# PWM-24Route.net
KiCad netlist of a schematic drawn in EasyEDA Pro
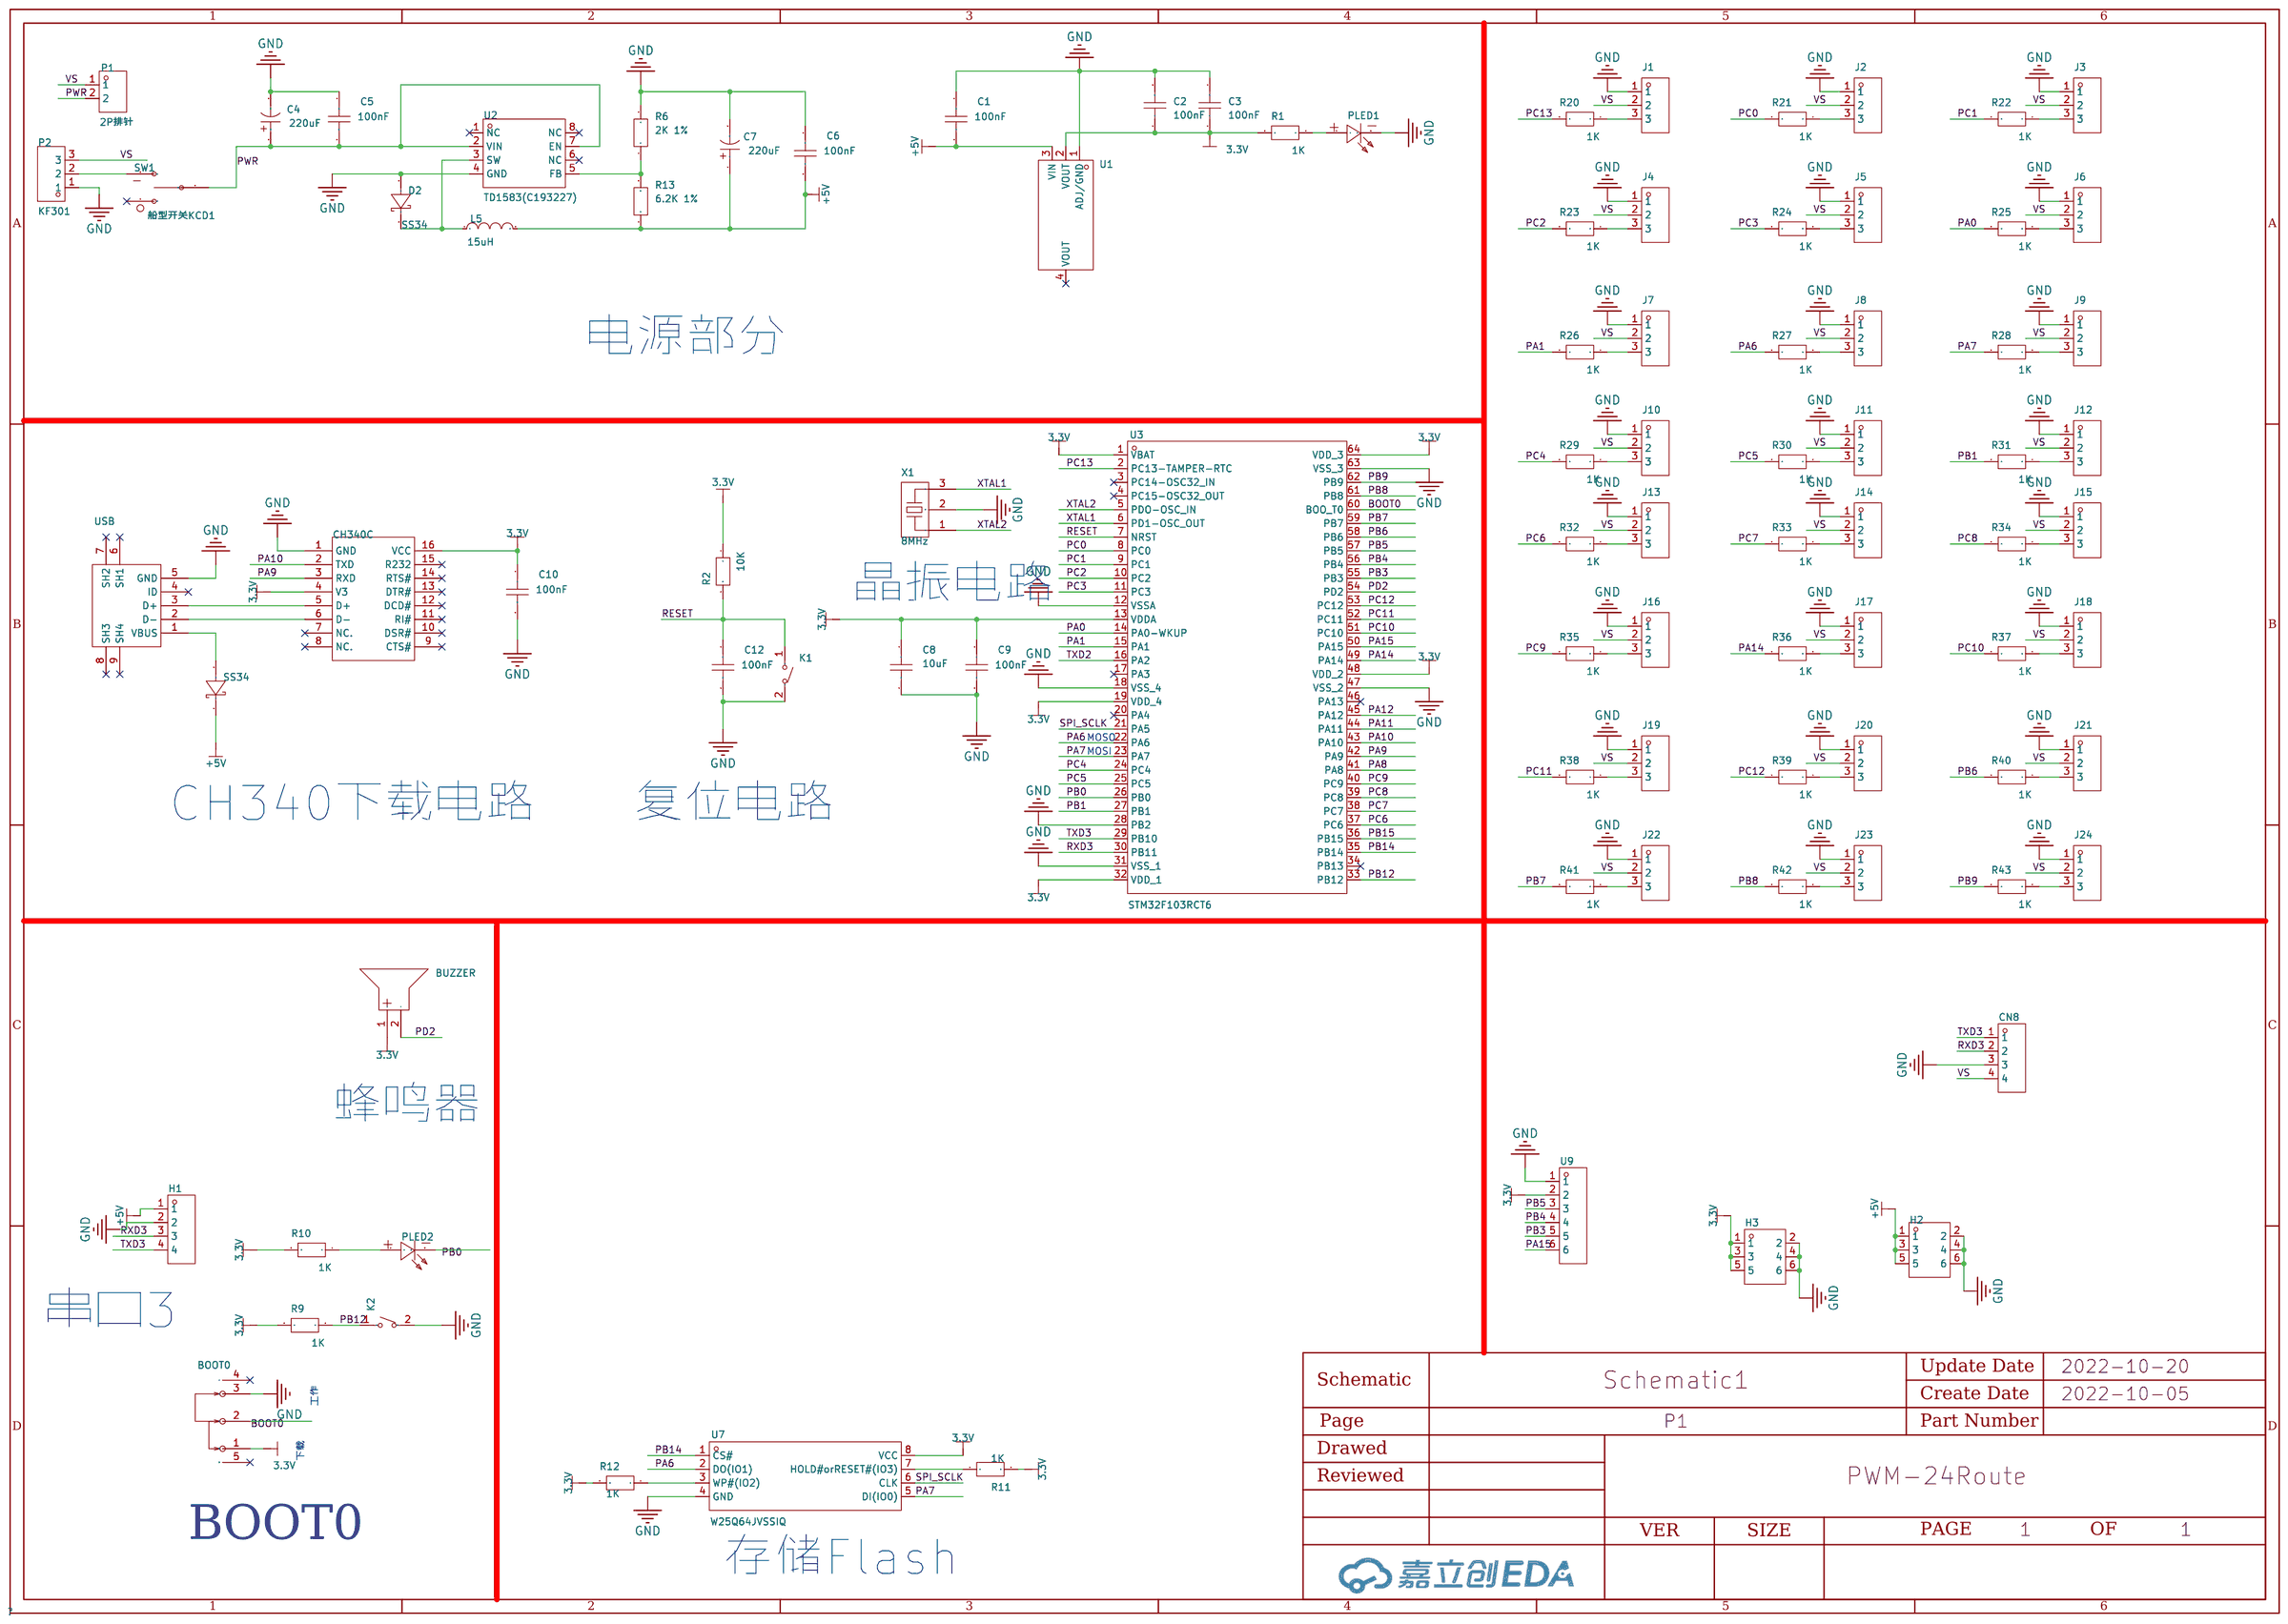
[diagram p0: schematic sheet]

(export (version "E")
  (design (tool "Eeschema 10.0.6"))
  (components
    (comp (ref "BOOT0")
      (value "SS-12F44-G5")
      (footprint "easyedapro:SW-TH_SS-12F44-G5")
      (fields (field (name "Manufacturer") "USAKRO(美韩)"))
      (libsource (lib "easyedapro") (part "SS-12F44-G5_C620367"))
    )
    (comp (ref "BUZZER")
      (value "5V,管脚间距8mm,外径10mm,高9.5mm")
      (footprint "easyedapro:BUZ-TH_BD12.0-P7.60-D0.6-FD")
      (libsource (lib "easyedapro") (part "5V,管脚间距8MM,外径10MM,高9.5MM"))
    )
    (comp (ref "C1")
      (value "100nF")
      (footprint "easyedapro:C0603")
      (description "容值:100nF;精度:±10%;额定电压:25V;温度系数:X7R;")
      (fields (field (name "Manufacturer Part") "C0603C104K3RAC") (field (name "Manufacturer") "KEMET(基美)"))
      (libsource (lib "easyedapro") (part "C0603C104K3RAC"))
    )
    (comp (ref "C2")
      (value "100nF")
      (footprint "easyedapro:C0603")
      (description "容值:100nF;精度:±10%;额定电压:25V;温度系数:X7R;")
      (fields (field (name "Manufacturer Part") "C0603C104K3RAC") (field (name "Manufacturer") "KEMET(基美)"))
      (libsource (lib "easyedapro") (part "C0603C104K3RAC"))
    )
    (comp (ref "C3")
      (value "100nF")
      (footprint "easyedapro:C0603")
      (description "容值:100nF;精度:±10%;额定电压:25V;温度系数:X7R;")
      (fields (field (name "Manufacturer Part") "C0603C104K3RAC") (field (name "Manufacturer") "KEMET(基美)"))
      (libsource (lib "easyedapro") (part "C0603C104K3RAC"))
    )
    (comp (ref "C4")
      (value "220uF")
      (footprint "easyedapro:CAP-SMD_BD6.3-L6.6-W6.6-FD")
      (description "容值:220uF;额定电压:16V;工作寿命:2000hrs@105;")
      (fields
        (field (name "Manufacturer Part") "RVT220UF16V67RV0015")
        (field (name "Manufacturer") "KNSCHA(科尼盛)")
      )
      (libsource (lib "easyedapro") (part "RVT220UF16V67RV0015"))
    )
    (comp (ref "C5")
      (value "100nF")
      (footprint "easyedapro:C0603")
      (description "容值:100nF;精度:±10%;额定电压:25V;温度系数:X7R;")
      (fields (field (name "Manufacturer Part") "C0603C104K3RAC") (field (name "Manufacturer") "KEMET(基美)"))
      (libsource (lib "easyedapro") (part "C0603C104K3RAC"))
    )
    (comp (ref "C6")
      (value "100nF")
      (footprint "easyedapro:C0603")
      (description "容值:100nF;精度:±10%;额定电压:25V;温度系数:X7R;")
      (fields (field (name "Manufacturer Part") "C0603C104K3RAC") (field (name "Manufacturer") "KEMET(基美)"))
      (libsource (lib "easyedapro") (part "C0603C104K3RAC"))
    )
    (comp (ref "C7")
      (value "220uF")
      (footprint "easyedapro:CAP-SMD_BD6.3-L6.6-W6.6-FD")
      (description "容值:220uF;额定电压:16V;工作寿命:2000hrs@105;")
      (fields
        (field (name "Manufacturer Part") "RVT220UF16V67RV0015")
        (field (name "Manufacturer") "KNSCHA(科尼盛)")
      )
      (libsource (lib "easyedapro") (part "RVT220UF16V67RV0015"))
    )
    (comp (ref "C8")
      (value "10uF")
      (footprint "easyedapro:C0603")
      (description "容值:100nF;精度:±10%;额定电压:25V;温度系数:X7R;")
      (fields (field (name "Manufacturer Part") "C0603C104K3RAC") (field (name "Manufacturer") "KEMET(基美)"))
      (libsource (lib "easyedapro") (part "C0603C104K3RAC"))
    )
    (comp (ref "C9")
      (value "100nF")
      (footprint "easyedapro:C0603")
      (description "容值:100nF;精度:±10%;额定电压:25V;温度系数:X7R;")
      (fields (field (name "Manufacturer Part") "C0603C104K3RAC") (field (name "Manufacturer") "KEMET(基美)"))
      (libsource (lib "easyedapro") (part "C0603C104K3RAC"))
    )
    (comp (ref "C10")
      (value "100nF")
      (footprint "easyedapro:C0603")
      (description "容值:100nF;精度:±10%;额定电压:25V;温度系数:X7R;")
      (fields (field (name "Manufacturer Part") "C0603C104K3RAC") (field (name "Manufacturer") "KEMET(基美)"))
      (libsource (lib "easyedapro") (part "C0603C104K3RAC"))
    )
    (comp (ref "C12")
      (value "100nF")
      (footprint "easyedapro:C0603")
      (description "容值:100nF;精度:±10%;额定电压:25V;温度系数:X7R;")
      (fields (field (name "Manufacturer Part") "C0603C104K3RAC") (field (name "Manufacturer") "KEMET(基美)"))
      (libsource (lib "easyedapro") (part "C0603C104K3RAC"))
    )
    (comp (ref "CH340C")
      (value "CH340C")
      (footprint "easyedapro:SOP-16_L10.0-W3.9-P1.27-LS6.0-BL")
      (description "类型:Transceiver;协议类别:USB 2.0;驱动器/接收器数:-;数据速率:2Mbps;")
      (fields (field (name "Manufacturer") "WCH(南京沁恒)"))
      (libsource (lib "easyedapro") (part "CH340C"))
    )
    (comp (ref "CN8")
      (value "HC-5264-4AW")
      (footprint "easyedapro:CONN-TH_4P-P2.50_HCTL_HC-5264-4AW")
      (description "参考系列:-;间距:2.5mm;插针结构:1x4P;排数:1;每排PIN数:4;行距:-;公母:公型插针;安装方式:弯插;额定电流:3A;工作温度范围:-25~+85;")
      (fields (field (name "Manufacturer") "HCTL(华灿天禄)"))
      (libsource (lib "easyedapro") (part "HC-5264-4AW"))
    )
    (comp (ref "D2")
      (value "SS34")
      (footprint "easyedapro:SMA_L4.3-W2.6-LS5.2-RD")
      (fields (field (name "Manufacturer") "TDD(台冠电子)"))
      (libsource (lib "easyedapro") (part "SS34_C3032484"))
    )
    (comp (ref "H1")
      (value "PM2.54-1*4")
      (footprint "easyedapro:HDR-TH_4P-P2.54-V-F")
      (description "安装类型:直插;")
      (fields (field (name "Manufacturer") "ZHOURI(洲日)"))
      (libsource (lib "easyedapro") (part "PM2.54-1*4"))
    )
    (comp (ref "H2")
      (value "PM2.54-2*3")
      (footprint "easyedapro:HDR-TH_6P-P2.54-V-F-R2-C3-S2.54")
      (description "安装类型:直插;")
      (fields (field (name "Manufacturer") "ZHOURI(洲日)"))
      (libsource (lib "easyedapro") (part "PM2.54-2*3"))
    )
    (comp (ref "H3")
      (value "PM2.54-2*3")
      (footprint "easyedapro:HDR-TH_6P-P2.54-V-F-R2-C3-S2.54")
      (description "安装类型:直插;")
      (fields (field (name "Manufacturer") "ZHOURI(洲日)"))
      (libsource (lib "easyedapro") (part "PM2.54-2*3"))
    )
    (comp (ref "J1")
      (value "TXM_3")
      (footprint "easyedapro:HDR-TH_3P-P2.54-V-M-A")
      (libsource (lib "easyedapro") (part "TXM_3"))
    )
    (comp (ref "J2")
      (value "TXM_3")
      (footprint "easyedapro:HDR-TH_3P-P2.54-V-M-A")
      (libsource (lib "easyedapro") (part "TXM_3"))
    )
    (comp (ref "J3")
      (value "TXM_3")
      (footprint "easyedapro:HDR-TH_3P-P2.54-V-M-A")
      (libsource (lib "easyedapro") (part "TXM_3"))
    )
    (comp (ref "J4")
      (value "TXM_3")
      (footprint "easyedapro:HDR-TH_3P-P2.54-V-M-A")
      (libsource (lib "easyedapro") (part "TXM_3"))
    )
    (comp (ref "J5")
      (value "TXM_3")
      (footprint "easyedapro:HDR-TH_3P-P2.54-V-M-A")
      (libsource (lib "easyedapro") (part "TXM_3"))
    )
    (comp (ref "J6")
      (value "TXM_3")
      (footprint "easyedapro:HDR-TH_3P-P2.54-V-M-A")
      (libsource (lib "easyedapro") (part "TXM_3"))
    )
    (comp (ref "J7")
      (value "TXM_3")
      (footprint "easyedapro:HDR-TH_3P-P2.54-V-M-A")
      (libsource (lib "easyedapro") (part "TXM_3"))
    )
    (comp (ref "J8")
      (value "TXM_3")
      (footprint "easyedapro:HDR-TH_3P-P2.54-V-M-A")
      (libsource (lib "easyedapro") (part "TXM_3"))
    )
    (comp (ref "J9")
      (value "TXM_3")
      (footprint "easyedapro:HDR-TH_3P-P2.54-V-M-A")
      (libsource (lib "easyedapro") (part "TXM_3"))
    )
    (comp (ref "J10")
      (value "TXM_3")
      (footprint "easyedapro:HDR-TH_3P-P2.54-V-M-A")
      (libsource (lib "easyedapro") (part "TXM_3"))
    )
    (comp (ref "J11")
      (value "TXM_3")
      (footprint "easyedapro:HDR-TH_3P-P2.54-V-M-A")
      (libsource (lib "easyedapro") (part "TXM_3"))
    )
    (comp (ref "J12")
      (value "TXM_3")
      (footprint "easyedapro:HDR-TH_3P-P2.54-V-M-A")
      (libsource (lib "easyedapro") (part "TXM_3"))
    )
    (comp (ref "J13")
      (value "TXM_3")
      (footprint "easyedapro:HDR-TH_3P-P2.54-V-M-A")
      (libsource (lib "easyedapro") (part "TXM_3"))
    )
    (comp (ref "J14")
      (value "TXM_3")
      (footprint "easyedapro:HDR-TH_3P-P2.54-V-M-A")
      (libsource (lib "easyedapro") (part "TXM_3"))
    )
    (comp (ref "J15")
      (value "TXM_3")
      (footprint "easyedapro:HDR-TH_3P-P2.54-V-M-A")
      (libsource (lib "easyedapro") (part "TXM_3"))
    )
    (comp (ref "J16")
      (value "TXM_3")
      (footprint "easyedapro:HDR-TH_3P-P2.54-V-M-A")
      (libsource (lib "easyedapro") (part "TXM_3"))
    )
    (comp (ref "J17")
      (value "TXM_3")
      (footprint "easyedapro:HDR-TH_3P-P2.54-V-M-A")
      (libsource (lib "easyedapro") (part "TXM_3"))
    )
    (comp (ref "J18")
      (value "TXM_3")
      (footprint "easyedapro:HDR-TH_3P-P2.54-V-M-A")
      (libsource (lib "easyedapro") (part "TXM_3"))
    )
    (comp (ref "J19")
      (value "TXM_3")
      (footprint "easyedapro:HDR-TH_3P-P2.54-V-M-A")
      (libsource (lib "easyedapro") (part "TXM_3"))
    )
    (comp (ref "J20")
      (value "TXM_3")
      (footprint "easyedapro:HDR-TH_3P-P2.54-V-M-A")
      (libsource (lib "easyedapro") (part "TXM_3"))
    )
    (comp (ref "J21")
      (value "TXM_3")
      (footprint "easyedapro:HDR-TH_3P-P2.54-V-M-A")
      (libsource (lib "easyedapro") (part "TXM_3"))
    )
    (comp (ref "J22")
      (value "TXM_3")
      (footprint "easyedapro:HDR-TH_3P-P2.54-V-M-A")
      (libsource (lib "easyedapro") (part "TXM_3"))
    )
    (comp (ref "J23")
      (value "TXM_3")
      (footprint "easyedapro:HDR-TH_3P-P2.54-V-M-A")
      (libsource (lib "easyedapro") (part "TXM_3"))
    )
    (comp (ref "J24")
      (value "TXM_3")
      (footprint "easyedapro:HDR-TH_3P-P2.54-V-M-A")
      (libsource (lib "easyedapro") (part "TXM_3"))
    )
    (comp (ref "K1")
      (value "KEY")
      (footprint "easyedapro:SW-SMD_L6.0-W3.7-LS8.0")
      (libsource (lib "easyedapro") (part "KEY_C9900023212"))
    )
    (comp (ref "K2")
      (value "KEY")
      (footprint "easyedapro:SW-SMD_L6.0-W3.7-LS8.0")
      (libsource (lib "easyedapro") (part "KEY_C9900023212"))
    )
    (comp (ref "L5")
      (value "15uH")
      (footprint "easyedapro:IND-SMD_L7.0-W6.6_FXL0630")
      (description "电感值:15uH;精度:±20%;额定电流:3A;饱和电流(Isat):4.5A;直流电阻(DCR):104m;")
      (fields (field (name "Manufacturer Part") "FXL0630-150-M") (field (name "Manufacturer") "cjiang(长江微电)"))
      (libsource (lib "easyedapro") (part "FXL0630-150-M"))
    )
    (comp (ref "P1")
      (value "2P排针")
      (footprint "easyedapro:HDR-TH_2P-P2.54-V-M-1")
      (fields (field (name "Manufacturer Part") "HDR1X2"))
      (libsource (lib "easyedapro") (part "HDR1X2"))
    )
    (comp (ref "P2")
      (value "KF301")
      (footprint "easyedapro:CONN-TH_3P-P5.00_KF301-5.0-3P")
      (description "间距:5mm;排数:1;每排PIN数:3;安装方式:直针;额定电流:17A;额定电压:250V;线规 - AWG:14~22;线规 - mm?:1.5;工作温度范围:-30~+120;颜色:蓝色;")
      (fields (field (name "Manufacturer Part") "KF301-5.0-3P") (field (name "Manufacturer") "KEFA(科发)"))
      (libsource (lib "easyedapro") (part "KF301-5.0-3P"))
    )
    (comp (ref "PLED1")
      (value "HSMQ-C191")
      (footprint "easyedapro:LED-SMD_L1.6-W0.8-R-RD")
      (fields (field (name "Manufacturer") "AVAGO(安华高)"))
      (libsource (lib "easyedapro") (part "HSMQ-C191"))
    )
    (comp (ref "PLED2")
      (value "HSMQ-C191")
      (footprint "easyedapro:LED-SMD_L1.6-W0.8-R-RD")
      (fields (field (name "Manufacturer") "AVAGO(安华高)"))
      (libsource (lib "easyedapro") (part "HSMQ-C191"))
    )
    (comp (ref "R1")
      (value "1K")
      (footprint "easyedapro:R0603")
      (fields (field (name "Manufacturer Part") "SCR0603F8R06") (field (name "Manufacturer") "VO(翔胜)"))
      (libsource (lib "easyedapro") (part "SCR0603F8R06"))
    )
    (comp (ref "R2")
      (value "10K")
      (footprint "easyedapro:R0603")
      (fields (field (name "Manufacturer Part") "SCR0603F8R06") (field (name "Manufacturer") "VO(翔胜)"))
      (libsource (lib "easyedapro") (part "SCR0603F8R06"))
    )
    (comp (ref "R6")
      (value "2K 1%")
      (footprint "easyedapro:R0603")
      (fields (field (name "Manufacturer Part") "SCR0603F8R06") (field (name "Manufacturer") "VO(翔胜)"))
      (libsource (lib "easyedapro") (part "SCR0603F8R06"))
    )
    (comp (ref "R9")
      (value "1K")
      (footprint "easyedapro:R0603")
      (fields (field (name "Manufacturer Part") "SCR0603F8R06") (field (name "Manufacturer") "VO(翔胜)"))
      (libsource (lib "easyedapro") (part "SCR0603F8R06"))
    )
    (comp (ref "R10")
      (value "1K")
      (footprint "easyedapro:R0603")
      (fields (field (name "Manufacturer Part") "SCR0603F8R06") (field (name "Manufacturer") "VO(翔胜)"))
      (libsource (lib "easyedapro") (part "SCR0603F8R06"))
    )
    (comp (ref "R11")
      (value "1K")
      (footprint "easyedapro:R0603")
      (fields (field (name "Manufacturer Part") "SCR0603F8R06") (field (name "Manufacturer") "VO(翔胜)"))
      (libsource (lib "easyedapro") (part "SCR0603F8R06"))
    )
    (comp (ref "R12")
      (value "1K")
      (footprint "easyedapro:R0603")
      (fields (field (name "Manufacturer Part") "SCR0603F8R06") (field (name "Manufacturer") "VO(翔胜)"))
      (libsource (lib "easyedapro") (part "SCR0603F8R06"))
    )
    (comp (ref "R13")
      (value "6.2K 1%")
      (footprint "easyedapro:R0603")
      (fields (field (name "Manufacturer Part") "SCR0603F8R06") (field (name "Manufacturer") "VO(翔胜)"))
      (libsource (lib "easyedapro") (part "SCR0603F8R06"))
    )
    (comp (ref "R20")
      (value "1K")
      (footprint "easyedapro:R0603")
      (fields (field (name "Manufacturer Part") "SCR0603F8R06") (field (name "Manufacturer") "VO(翔胜)"))
      (libsource (lib "easyedapro") (part "SCR0603F8R06"))
    )
    (comp (ref "R21")
      (value "1K")
      (footprint "easyedapro:R0603")
      (fields (field (name "Manufacturer Part") "SCR0603F8R06") (field (name "Manufacturer") "VO(翔胜)"))
      (libsource (lib "easyedapro") (part "SCR0603F8R06"))
    )
    (comp (ref "R22")
      (value "1K")
      (footprint "easyedapro:R0603")
      (fields (field (name "Manufacturer Part") "SCR0603F8R06") (field (name "Manufacturer") "VO(翔胜)"))
      (libsource (lib "easyedapro") (part "SCR0603F8R06"))
    )
    (comp (ref "R23")
      (value "1K")
      (footprint "easyedapro:R0603")
      (fields (field (name "Manufacturer Part") "SCR0603F8R06") (field (name "Manufacturer") "VO(翔胜)"))
      (libsource (lib "easyedapro") (part "SCR0603F8R06"))
    )
    (comp (ref "R24")
      (value "1K")
      (footprint "easyedapro:R0603")
      (fields (field (name "Manufacturer Part") "SCR0603F8R06") (field (name "Manufacturer") "VO(翔胜)"))
      (libsource (lib "easyedapro") (part "SCR0603F8R06"))
    )
    (comp (ref "R25")
      (value "1K")
      (footprint "easyedapro:R0603")
      (fields (field (name "Manufacturer Part") "SCR0603F8R06") (field (name "Manufacturer") "VO(翔胜)"))
      (libsource (lib "easyedapro") (part "SCR0603F8R06"))
    )
    (comp (ref "R26")
      (value "1K")
      (footprint "easyedapro:R0603")
      (fields (field (name "Manufacturer Part") "SCR0603F8R06") (field (name "Manufacturer") "VO(翔胜)"))
      (libsource (lib "easyedapro") (part "SCR0603F8R06"))
    )
    (comp (ref "R27")
      (value "1K")
      (footprint "easyedapro:R0603")
      (fields (field (name "Manufacturer Part") "SCR0603F8R06") (field (name "Manufacturer") "VO(翔胜)"))
      (libsource (lib "easyedapro") (part "SCR0603F8R06"))
    )
    (comp (ref "R28")
      (value "1K")
      (footprint "easyedapro:R0603")
      (fields (field (name "Manufacturer Part") "SCR0603F8R06") (field (name "Manufacturer") "VO(翔胜)"))
      (libsource (lib "easyedapro") (part "SCR0603F8R06"))
    )
    (comp (ref "R29")
      (value "1K")
      (footprint "easyedapro:R0603")
      (fields (field (name "Manufacturer Part") "SCR0603F8R06") (field (name "Manufacturer") "VO(翔胜)"))
      (libsource (lib "easyedapro") (part "SCR0603F8R06"))
    )
    (comp (ref "R30")
      (value "1K")
      (footprint "easyedapro:R0603")
      (fields (field (name "Manufacturer Part") "SCR0603F8R06") (field (name "Manufacturer") "VO(翔胜)"))
      (libsource (lib "easyedapro") (part "SCR0603F8R06"))
    )
    (comp (ref "R31")
      (value "1K")
      (footprint "easyedapro:R0603")
      (fields (field (name "Manufacturer Part") "SCR0603F8R06") (field (name "Manufacturer") "VO(翔胜)"))
      (libsource (lib "easyedapro") (part "SCR0603F8R06"))
    )
    (comp (ref "R32")
      (value "1K")
      (footprint "easyedapro:R0603")
      (fields (field (name "Manufacturer Part") "SCR0603F8R06") (field (name "Manufacturer") "VO(翔胜)"))
      (libsource (lib "easyedapro") (part "SCR0603F8R06"))
    )
    (comp (ref "R33")
      (value "1K")
      (footprint "easyedapro:R0603")
      (fields (field (name "Manufacturer Part") "SCR0603F8R06") (field (name "Manufacturer") "VO(翔胜)"))
      (libsource (lib "easyedapro") (part "SCR0603F8R06"))
    )
    (comp (ref "R34")
      (value "1K")
      (footprint "easyedapro:R0603")
      (fields (field (name "Manufacturer Part") "SCR0603F8R06") (field (name "Manufacturer") "VO(翔胜)"))
      (libsource (lib "easyedapro") (part "SCR0603F8R06"))
    )
    (comp (ref "R35")
      (value "1K")
      (footprint "easyedapro:R0603")
      (fields (field (name "Manufacturer Part") "SCR0603F8R06") (field (name "Manufacturer") "VO(翔胜)"))
      (libsource (lib "easyedapro") (part "SCR0603F8R06"))
    )
    (comp (ref "R36")
      (value "1K")
      (footprint "easyedapro:R0603")
      (fields (field (name "Manufacturer Part") "SCR0603F8R06") (field (name "Manufacturer") "VO(翔胜)"))
      (libsource (lib "easyedapro") (part "SCR0603F8R06"))
    )
    (comp (ref "R37")
      (value "1K")
      (footprint "easyedapro:R0603")
      (fields (field (name "Manufacturer Part") "SCR0603F8R06") (field (name "Manufacturer") "VO(翔胜)"))
      (libsource (lib "easyedapro") (part "SCR0603F8R06"))
    )
    (comp (ref "R38")
      (value "1K")
      (footprint "easyedapro:R0603")
      (fields (field (name "Manufacturer Part") "SCR0603F8R06") (field (name "Manufacturer") "VO(翔胜)"))
      (libsource (lib "easyedapro") (part "SCR0603F8R06"))
    )
    (comp (ref "R39")
      (value "1K")
      (footprint "easyedapro:R0603")
      (fields (field (name "Manufacturer Part") "SCR0603F8R06") (field (name "Manufacturer") "VO(翔胜)"))
      (libsource (lib "easyedapro") (part "SCR0603F8R06"))
    )
    (comp (ref "R40")
      (value "1K")
      (footprint "easyedapro:R0603")
      (fields (field (name "Manufacturer Part") "SCR0603F8R06") (field (name "Manufacturer") "VO(翔胜)"))
      (libsource (lib "easyedapro") (part "SCR0603F8R06"))
    )
    (comp (ref "R41")
      (value "1K")
      (footprint "easyedapro:R0603")
      (fields (field (name "Manufacturer Part") "SCR0603F8R06") (field (name "Manufacturer") "VO(翔胜)"))
      (libsource (lib "easyedapro") (part "SCR0603F8R06"))
    )
    (comp (ref "R42")
      (value "1K")
      (footprint "easyedapro:R0603")
      (fields (field (name "Manufacturer Part") "SCR0603F8R06") (field (name "Manufacturer") "VO(翔胜)"))
      (libsource (lib "easyedapro") (part "SCR0603F8R06"))
    )
    (comp (ref "R43")
      (value "1K")
      (footprint "easyedapro:R0603")
      (fields (field (name "Manufacturer Part") "SCR0603F8R06") (field (name "Manufacturer") "VO(翔胜)"))
      (libsource (lib "easyedapro") (part "SCR0603F8R06"))
    )
    (comp (ref "SS34")
      (value "SS34")
      (footprint "easyedapro:SMA_L4.3-W2.6-LS5.2-RD")
      (fields (field (name "Manufacturer") "TDD(台冠电子)"))
      (libsource (lib "easyedapro") (part "SS34_C3032484"))
    )
    (comp (ref "SW1")
      (value "船型开关KCD1")
      (footprint "easyedapro:SW-TH_3P-KCD11-2")
      (fields (field (name "Manufacturer Part") "KCD11 10*15"))
      (libsource (lib "easyedapro") (part "KCD11 10*15"))
    )
    (comp (ref "U1")
      (value "AMS117-3.3")
      (footprint "easyedapro:SOT-223_L6.5-W3.5-P2.30-LS7.0-BR")
      (description "输出类型:固定;输出极性:正;输出通道数:1;最大输入电压:18V;输出电压:3.3V;压差:1.4V@(1A);输出电流:1A;电源纹波抑制比(PRSS):70dB@(120Hz);")
      (fields (field (name "Manufacturer Part") "AMS1117-3.3") (field (name "Manufacturer") "Slkor(萨科微)"))
      (libsource (lib "easyedapro") (part "AMS1117-3.3_C426566"))
    )
    (comp (ref "U2")
      (value "TD1583(C193227)")
      (footprint "easyedapro:SOP-8_L5.0-W4.0-P1.27-LS6.0-BL")
      (description "功能类型:降压型;同步整流:否;输出通道数:1;拓扑结构:降压式;输入电压:3.6V~28V;输出电压:1.222V~26V;输出电流(最大值):3A;开关频率:380kHz;")
      (fields (field (name "Manufacturer Part") "TD1583") (field (name "Manufacturer") "Techcode(泰德)"))
      (libsource (lib "easyedapro") (part "TD1583"))
    )
    (comp (ref "U3")
      (value "STM32F103RCT6")
      (footprint "easyedapro:LQFP-64_L10.0-W10.0-P0.50-LS12.0-BL")
      (description "主频（MAX):72MHz;工作电压:2V ~ 3.6V;")
      (fields (field (name "Manufacturer") "ST(意法半导体)"))
      (libsource (lib "easyedapro") (part "STM32F103RCT6"))
    )
    (comp (ref "U7")
      (value "W25Q64JVSSIQ")
      (footprint "easyedapro:SOIC-8_L5.3-W5.3-P1.27-LS8.0-BL")
      (description "存储器类型:-;存储器构架(格式):-;技术:-;存储器容量:-;时钟频率:-;存储器接口类型:-;")
      (fields (field (name "Manufacturer") "WINBOND(华邦)"))
      (libsource (lib "easyedapro") (part "W25Q64JVSSIQ_C179171"))
    )
    (comp (ref "U9")
      (value "双塑单排排针6PIN2.54间距")
      (footprint "easyedapro:HDR-TH_6P-P2.54-V-M-A-1")
      (libsource (lib "easyedapro") (part "双塑单排排针6PIN2.54间距"))
    )
    (comp (ref "USB")
      (value "MicroXNJ")
      (footprint "easyedapro:MICRO-USB-SMD_MICROXNJ")
      (description "连接器类型:Micro-B;标准:USB 2.0;公母:母座;触点数量:5;端口数量:1;安装方式:卧贴;额定电流 - 电源:1A;工作温度范围:-20~+85;")
      (fields (field (name "Manufacturer") "SHOU HAN(首韩)"))
      (libsource (lib "easyedapro") (part "MICROXNJ"))
    )
    (comp (ref "X1")
      (value "8MHz")
      (footprint "easyedapro:OSC-SMD_3P-L3.2-W1.3-P1.2-L")
      (description "频率:8MHz;频率容差:±0.1%;内藏负载电容:33pF;谐振阻抗:40;")
      (fields
        (field (name "Manufacturer Part") "CSTCE8M00G15C99-R0")
        (field (name "Manufacturer") "muRata(村田)")
      )
      (libsource (lib "easyedapro") (part "CSTCE8M00G15C99-R0"))
    )
  )
  (nets
    (net (code "1") (name "+5V") (class "Default")
      (node (ref "C1") (pin "2") (pinfunction "2_2") (pintype "input"))
      (node (ref "C6") (pin "2") (pinfunction "2_2") (pintype "input"))
      (node (ref "C7") (pin "1") (pinfunction "1_1") (pintype "input"))
      (node (ref "H1") (pin "1") (pinfunction "1_1") (pintype "input"))
      (node (ref "H2") (pin "1") (pinfunction "1_1") (pintype "input"))
      (node (ref "H2") (pin "3") (pinfunction "3_3") (pintype "input"))
      (node (ref "H2") (pin "5") (pinfunction "5_5") (pintype "input"))
      (node (ref "L5") (pin "2") (pinfunction "2_2") (pintype "input"))
      (node (ref "R13") (pin "1") (pinfunction "1_1") (pintype "input"))
      (node (ref "SS34") (pin "1") (pinfunction "K_1") (pintype "input"))
      (node (ref "U1") (pin "3") (pinfunction "VIN_3") (pintype "input"))
    )
    (net (code "2") (name "/BOOT0") (class "Default")
      (node (ref "BOOT0") (pin "2") (pinfunction "2_2") (pintype "input"))
      (node (ref "U3") (pin "60") (pinfunction "BOO_T0_60") (pintype "input"))
    )
    (net (code "3") (name "/PA0") (class "Default")
      (node (ref "R25") (pin "2") (pinfunction "2_2") (pintype "input"))
      (node (ref "U3") (pin "14") (pinfunction "PA0-WKUP_14") (pintype "input"))
    )
    (net (code "4") (name "/PA1") (class "Default")
      (node (ref "R26") (pin "2") (pinfunction "2_2") (pintype "input"))
      (node (ref "U3") (pin "15") (pinfunction "PA1_15") (pintype "input"))
    )
    (net (code "5") (name "/PA6") (class "Default")
      (node (ref "R27") (pin "2") (pinfunction "2_2") (pintype "input"))
      (node (ref "U3") (pin "22") (pinfunction "PA6_22") (pintype "input"))
      (node (ref "U7") (pin "2") (pinfunction "DO(IO1)_2") (pintype "input"))
    )
    (net (code "6") (name "/PA7") (class "Default")
      (node (ref "R28") (pin "2") (pinfunction "2_2") (pintype "input"))
      (node (ref "U3") (pin "23") (pinfunction "PA7_23") (pintype "input"))
      (node (ref "U7") (pin "5") (pinfunction "DI(IO0)_5") (pintype "input"))
    )
    (net (code "7") (name "/PA8") (class "Default")
      (node (ref "U3") (pin "41") (pinfunction "PA8_41") (pintype "input"))
    )
    (net (code "8") (name "/PA9") (class "Default")
      (node (ref "CH340C") (pin "3") (pinfunction "RXD_3") (pintype "input"))
      (node (ref "U3") (pin "42") (pinfunction "PA9_42") (pintype "input"))
    )
    (net (code "9") (name "/PA10") (class "Default")
      (node (ref "CH340C") (pin "2") (pinfunction "TXD_2") (pintype "input"))
      (node (ref "U3") (pin "43") (pinfunction "PA10_43") (pintype "input"))
    )
    (net (code "10") (name "/PA11") (class "Default")
      (node (ref "U3") (pin "44") (pinfunction "PA11_44") (pintype "input"))
    )
    (net (code "11") (name "/PA12") (class "Default")
      (node (ref "U3") (pin "45") (pinfunction "PA12_45") (pintype "input"))
    )
    (net (code "12") (name "/PA14") (class "Default")
      (node (ref "R36") (pin "2") (pinfunction "2_2") (pintype "input"))
      (node (ref "U3") (pin "49") (pinfunction "PA14_49") (pintype "input"))
    )
    (net (code "13") (name "/PA15") (class "Default")
      (node (ref "U3") (pin "50") (pinfunction "PA15_50") (pintype "input"))
      (node (ref "U9") (pin "6") (pinfunction "6_6") (pintype "input"))
    )
    (net (code "14") (name "/PB0") (class "Default")
      (node (ref "PLED2") (pin "2") (pinfunction "C_2") (pintype "input"))
      (node (ref "U3") (pin "26") (pinfunction "PB0_26") (pintype "input"))
    )
    (net (code "15") (name "/PB1") (class "Default")
      (node (ref "R31") (pin "2") (pinfunction "2_2") (pintype "input"))
      (node (ref "U3") (pin "27") (pinfunction "PB1_27") (pintype "input"))
    )
    (net (code "16") (name "/PB3") (class "Default")
      (node (ref "U3") (pin "55") (pinfunction "PB3_55") (pintype "input"))
      (node (ref "U9") (pin "5") (pinfunction "5_5") (pintype "input"))
    )
    (net (code "17") (name "/PB4") (class "Default")
      (node (ref "U3") (pin "56") (pinfunction "PB4_56") (pintype "input"))
      (node (ref "U9") (pin "4") (pinfunction "4_4") (pintype "input"))
    )
    (net (code "18") (name "/PB5") (class "Default")
      (node (ref "U3") (pin "57") (pinfunction "PB5_57") (pintype "input"))
      (node (ref "U9") (pin "3") (pinfunction "3_3") (pintype "input"))
    )
    (net (code "19") (name "/PB6") (class "Default")
      (node (ref "R40") (pin "2") (pinfunction "2_2") (pintype "input"))
      (node (ref "U3") (pin "58") (pinfunction "PB6_58") (pintype "input"))
    )
    (net (code "20") (name "/PB7") (class "Default")
      (node (ref "R41") (pin "2") (pinfunction "2_2") (pintype "input"))
      (node (ref "U3") (pin "59") (pinfunction "PB7_59") (pintype "input"))
    )
    (net (code "21") (name "/PB8") (class "Default")
      (node (ref "R42") (pin "2") (pinfunction "2_2") (pintype "input"))
      (node (ref "U3") (pin "61") (pinfunction "PB8_61") (pintype "input"))
    )
    (net (code "22") (name "/PB9") (class "Default")
      (node (ref "R43") (pin "2") (pinfunction "2_2") (pintype "input"))
      (node (ref "U3") (pin "62") (pinfunction "PB9_62") (pintype "input"))
    )
    (net (code "23") (name "/PB12") (class "Default")
      (node (ref "K2") (pin "1") (pinfunction "1_1") (pintype "input"))
      (node (ref "R9") (pin "1") (pinfunction "1_1") (pintype "input"))
      (node (ref "U3") (pin "33") (pinfunction "PB12_33") (pintype "input"))
    )
    (net (code "24") (name "/PB14") (class "Default")
      (node (ref "U3") (pin "35") (pinfunction "PB14_35") (pintype "input"))
      (node (ref "U7") (pin "1") (pinfunction "CS#_1") (pintype "input"))
    )
    (net (code "25") (name "/PB15") (class "Default")
      (node (ref "U3") (pin "36") (pinfunction "PB15_36") (pintype "input"))
    )
    (net (code "26") (name "/PC0") (class "Default")
      (node (ref "R21") (pin "2") (pinfunction "2_2") (pintype "input"))
      (node (ref "U3") (pin "8") (pinfunction "PC0_8") (pintype "input"))
    )
    (net (code "27") (name "/PC1") (class "Default")
      (node (ref "R22") (pin "2") (pinfunction "2_2") (pintype "input"))
      (node (ref "U3") (pin "9") (pinfunction "PC1_9") (pintype "input"))
    )
    (net (code "28") (name "/PC2") (class "Default")
      (node (ref "R23") (pin "2") (pinfunction "2_2") (pintype "input"))
      (node (ref "U3") (pin "10") (pinfunction "PC2_10") (pintype "input"))
    )
    (net (code "29") (name "/PC3") (class "Default")
      (node (ref "R24") (pin "2") (pinfunction "2_2") (pintype "input"))
      (node (ref "U3") (pin "11") (pinfunction "PC3_11") (pintype "input"))
    )
    (net (code "30") (name "/PC4") (class "Default")
      (node (ref "R29") (pin "2") (pinfunction "2_2") (pintype "input"))
      (node (ref "U3") (pin "24") (pinfunction "PC4_24") (pintype "input"))
    )
    (net (code "31") (name "/PC5") (class "Default")
      (node (ref "R30") (pin "2") (pinfunction "2_2") (pintype "input"))
      (node (ref "U3") (pin "25") (pinfunction "PC5_25") (pintype "input"))
    )
    (net (code "32") (name "/PC6") (class "Default")
      (node (ref "R32") (pin "2") (pinfunction "2_2") (pintype "input"))
      (node (ref "U3") (pin "37") (pinfunction "PC6_37") (pintype "input"))
    )
    (net (code "33") (name "/PC7") (class "Default")
      (node (ref "R33") (pin "2") (pinfunction "2_2") (pintype "input"))
      (node (ref "U3") (pin "38") (pinfunction "PC7_38") (pintype "input"))
    )
    (net (code "34") (name "/PC8") (class "Default")
      (node (ref "R34") (pin "2") (pinfunction "2_2") (pintype "input"))
      (node (ref "U3") (pin "39") (pinfunction "PC8_39") (pintype "input"))
    )
    (net (code "35") (name "/PC9") (class "Default")
      (node (ref "R35") (pin "2") (pinfunction "2_2") (pintype "input"))
      (node (ref "U3") (pin "40") (pinfunction "PC9_40") (pintype "input"))
    )
    (net (code "36") (name "/PC10") (class "Default")
      (node (ref "R37") (pin "2") (pinfunction "2_2") (pintype "input"))
      (node (ref "U3") (pin "51") (pinfunction "PC10_51") (pintype "input"))
    )
    (net (code "37") (name "/PC11") (class "Default")
      (node (ref "R38") (pin "2") (pinfunction "2_2") (pintype "input"))
      (node (ref "U3") (pin "52") (pinfunction "PC11_52") (pintype "input"))
    )
    (net (code "38") (name "/PC12") (class "Default")
      (node (ref "R39") (pin "2") (pinfunction "2_2") (pintype "input"))
      (node (ref "U3") (pin "53") (pinfunction "PC12_53") (pintype "input"))
    )
    (net (code "39") (name "/PC13") (class "Default")
      (node (ref "R20") (pin "2") (pinfunction "2_2") (pintype "input"))
      (node (ref "U3") (pin "2") (pinfunction "PC13-TAMPER-RTC_2") (pintype "input"))
    )
    (net (code "40") (name "/PD2") (class "Default")
      (node (ref "BUZZER") (pin "2") (pinfunction "-_2") (pintype "input"))
      (node (ref "U3") (pin "54") (pinfunction "PD2_54") (pintype "input"))
    )
    (net (code "41") (name "/PWR") (class "Default")
      (node (ref "C4") (pin "1") (pinfunction "1_1") (pintype "input"))
      (node (ref "C5") (pin "2") (pinfunction "2_2") (pintype "input"))
      (node (ref "P1") (pin "2") (pinfunction "2_2") (pintype "input"))
      (node (ref "SW1") (pin "2") (pinfunction "2_2") (pintype "input"))
      (node (ref "U2") (pin "2") (pinfunction "VIN_2") (pintype "input"))
      (node (ref "U2") (pin "7") (pinfunction "EN_7") (pintype "input"))
    )
    (net (code "42") (name "/RESET") (class "Default")
      (node (ref "C12") (pin "1") (pinfunction "1_1") (pintype "input"))
      (node (ref "K1") (pin "1") (pinfunction "1_1") (pintype "input"))
      (node (ref "R2") (pin "2") (pinfunction "2_2") (pintype "input"))
      (node (ref "U3") (pin "7") (pinfunction "NRST_7") (pintype "input"))
    )
    (net (code "43") (name "/RXD3") (class "Default")
      (node (ref "CN8") (pin "2") (pinfunction "2_2") (pintype "input"))
      (node (ref "H1") (pin "3") (pinfunction "3_3") (pintype "input"))
      (node (ref "U3") (pin "30") (pinfunction "PB11_30") (pintype "input"))
    )
    (net (code "44") (name "/SPI_SCLK") (class "Default")
      (node (ref "U3") (pin "21") (pinfunction "PA5_21") (pintype "input"))
      (node (ref "U7") (pin "6") (pinfunction "CLK_6") (pintype "input"))
    )
    (net (code "45") (name "/TXD2") (class "Default")
      (node (ref "U3") (pin "16") (pinfunction "PA2_16") (pintype "input"))
    )
    (net (code "46") (name "/TXD3") (class "Default")
      (node (ref "CN8") (pin "1") (pinfunction "1_1") (pintype "input"))
      (node (ref "H1") (pin "4") (pinfunction "4_4") (pintype "input"))
      (node (ref "U3") (pin "29") (pinfunction "PB10_29") (pintype "input"))
    )
    (net (code "47") (name "/VS") (class "Default")
      (node (ref "CN8") (pin "4") (pinfunction "4_4") (pintype "input"))
      (node (ref "J1") (pin "2") (pinfunction "2_2") (pintype "input"))
      (node (ref "J10") (pin "2") (pinfunction "2_2") (pintype "input"))
      (node (ref "J11") (pin "2") (pinfunction "2_2") (pintype "input"))
      (node (ref "J12") (pin "2") (pinfunction "2_2") (pintype "input"))
      (node (ref "J13") (pin "2") (pinfunction "2_2") (pintype "input"))
      (node (ref "J14") (pin "2") (pinfunction "2_2") (pintype "input"))
      (node (ref "J15") (pin "2") (pinfunction "2_2") (pintype "input"))
      (node (ref "J16") (pin "2") (pinfunction "2_2") (pintype "input"))
      (node (ref "J17") (pin "2") (pinfunction "2_2") (pintype "input"))
      (node (ref "J18") (pin "2") (pinfunction "2_2") (pintype "input"))
      (node (ref "J19") (pin "2") (pinfunction "2_2") (pintype "input"))
      (node (ref "J2") (pin "2") (pinfunction "2_2") (pintype "input"))
      (node (ref "J20") (pin "2") (pinfunction "2_2") (pintype "input"))
      (node (ref "J21") (pin "2") (pinfunction "2_2") (pintype "input"))
      (node (ref "J22") (pin "2") (pinfunction "2_2") (pintype "input"))
      (node (ref "J23") (pin "2") (pinfunction "2_2") (pintype "input"))
      (node (ref "J24") (pin "2") (pinfunction "2_2") (pintype "input"))
      (node (ref "J3") (pin "2") (pinfunction "2_2") (pintype "input"))
      (node (ref "J4") (pin "2") (pinfunction "2_2") (pintype "input"))
      (node (ref "J5") (pin "2") (pinfunction "2_2") (pintype "input"))
      (node (ref "J6") (pin "2") (pinfunction "2_2") (pintype "input"))
      (node (ref "J7") (pin "2") (pinfunction "2_2") (pintype "input"))
      (node (ref "J8") (pin "2") (pinfunction "2_2") (pintype "input"))
      (node (ref "J9") (pin "2") (pinfunction "2_2") (pintype "input"))
      (node (ref "P1") (pin "1") (pinfunction "1_1") (pintype "input"))
      (node (ref "P2") (pin "3") (pinfunction "3_3") (pintype "input"))
    )
    (net (code "48") (name "/XTAL1") (class "Default")
      (node (ref "U3") (pin "6") (pinfunction "PD1-OSC_OUT_6") (pintype "input"))
      (node (ref "X1") (pin "3") (pinfunction "3_3") (pintype "input"))
    )
    (net (code "49") (name "/XTAL2") (class "Default")
      (node (ref "U3") (pin "5") (pinfunction "PDO-OSC_IN_5") (pintype "input"))
      (node (ref "X1") (pin "1") (pinfunction "1_1") (pintype "input"))
    )
    (net (code "50") (name "3.3V") (class "Default")
      (node (ref "BOOT0") (pin "1") (pinfunction "1_1") (pintype "input"))
      (node (ref "BUZZER") (pin "1") (pinfunction "+_1") (pintype "input"))
      (node (ref "C10") (pin "1") (pinfunction "1_1") (pintype "input"))
      (node (ref "C2") (pin "1") (pinfunction "1_1") (pintype "input"))
      (node (ref "C3") (pin "2") (pinfunction "2_2") (pintype "input"))
      (node (ref "C8") (pin "1") (pinfunction "1_1") (pintype "input"))
      (node (ref "C9") (pin "1") (pinfunction "1_1") (pintype "input"))
      (node (ref "CH340C") (pin "16") (pinfunction "VCC_16") (pintype "input"))
      (node (ref "CH340C") (pin "4") (pinfunction "V3_4") (pintype "input"))
      (node (ref "H3") (pin "1") (pinfunction "1_1") (pintype "input"))
      (node (ref "H3") (pin "3") (pinfunction "3_3") (pintype "input"))
      (node (ref "H3") (pin "5") (pinfunction "5_5") (pintype "input"))
      (node (ref "R1") (pin "2") (pinfunction "2_2") (pintype "input"))
      (node (ref "R10") (pin "2") (pinfunction "2_2") (pintype "input"))
      (node (ref "R11") (pin "2") (pinfunction "2_2") (pintype "input"))
      (node (ref "R12") (pin "2") (pinfunction "2_2") (pintype "input"))
      (node (ref "R2") (pin "1") (pinfunction "1_1") (pintype "input"))
      (node (ref "R9") (pin "2") (pinfunction "2_2") (pintype "input"))
      (node (ref "U1") (pin "2") (pinfunction "VOUT_2") (pintype "input"))
      (node (ref "U3") (pin "1") (pinfunction "VBAT_1") (pintype "input"))
      (node (ref "U3") (pin "13") (pinfunction "VDDA_13") (pintype "input"))
      (node (ref "U3") (pin "19") (pinfunction "VDD_4_19") (pintype "input"))
      (node (ref "U3") (pin "32") (pinfunction "VDD_1_32") (pintype "input"))
      (node (ref "U3") (pin "48") (pinfunction "VDD_2_48") (pintype "input"))
      (node (ref "U3") (pin "64") (pinfunction "VDD_3_64") (pintype "input"))
      (node (ref "U7") (pin "8") (pinfunction "VCC_8") (pintype "input"))
      (node (ref "U9") (pin "2") (pinfunction "2_2") (pintype "input"))
    )
    (net (code "51") (name "GND") (class "Default")
      (node (ref "BOOT0") (pin "3") (pinfunction "3_3") (pintype "input"))
      (node (ref "C1") (pin "1") (pinfunction "1_1") (pintype "input"))
      (node (ref "C10") (pin "2") (pinfunction "2_2") (pintype "input"))
      (node (ref "C12") (pin "2") (pinfunction "2_2") (pintype "input"))
      (node (ref "C2") (pin "2") (pinfunction "2_2") (pintype "input"))
      (node (ref "C3") (pin "1") (pinfunction "1_1") (pintype "input"))
      (node (ref "C4") (pin "2") (pinfunction "2_2") (pintype "input"))
      (node (ref "C5") (pin "1") (pinfunction "1_1") (pintype "input"))
      (node (ref "C6") (pin "1") (pinfunction "1_1") (pintype "input"))
      (node (ref "C7") (pin "2") (pinfunction "2_2") (pintype "input"))
      (node (ref "C8") (pin "2") (pinfunction "2_2") (pintype "input"))
      (node (ref "C9") (pin "2") (pinfunction "2_2") (pintype "input"))
      (node (ref "CH340C") (pin "1") (pinfunction "GND_1") (pintype "input"))
      (node (ref "CN8") (pin "3") (pinfunction "3_3") (pintype "input"))
      (node (ref "D2") (pin "2") (pinfunction "A_2") (pintype "input"))
      (node (ref "H1") (pin "2") (pinfunction "2_2") (pintype "input"))
      (node (ref "H2") (pin "2") (pinfunction "2_2") (pintype "input"))
      (node (ref "H2") (pin "4") (pinfunction "4_4") (pintype "input"))
      (node (ref "H2") (pin "6") (pinfunction "6_6") (pintype "input"))
      (node (ref "H3") (pin "2") (pinfunction "2_2") (pintype "input"))
      (node (ref "H3") (pin "4") (pinfunction "4_4") (pintype "input"))
      (node (ref "H3") (pin "6") (pinfunction "6_6") (pintype "input"))
      (node (ref "J1") (pin "1") (pinfunction "1_1") (pintype "input"))
      (node (ref "J10") (pin "1") (pinfunction "1_1") (pintype "input"))
      (node (ref "J11") (pin "1") (pinfunction "1_1") (pintype "input"))
      (node (ref "J12") (pin "1") (pinfunction "1_1") (pintype "input"))
      (node (ref "J13") (pin "1") (pinfunction "1_1") (pintype "input"))
      (node (ref "J14") (pin "1") (pinfunction "1_1") (pintype "input"))
      (node (ref "J15") (pin "1") (pinfunction "1_1") (pintype "input"))
      (node (ref "J16") (pin "1") (pinfunction "1_1") (pintype "input"))
      (node (ref "J17") (pin "1") (pinfunction "1_1") (pintype "input"))
      (node (ref "J18") (pin "1") (pinfunction "1_1") (pintype "input"))
      (node (ref "J19") (pin "1") (pinfunction "1_1") (pintype "input"))
      (node (ref "J2") (pin "1") (pinfunction "1_1") (pintype "input"))
      (node (ref "J20") (pin "1") (pinfunction "1_1") (pintype "input"))
      (node (ref "J21") (pin "1") (pinfunction "1_1") (pintype "input"))
      (node (ref "J22") (pin "1") (pinfunction "1_1") (pintype "input"))
      (node (ref "J23") (pin "1") (pinfunction "1_1") (pintype "input"))
      (node (ref "J24") (pin "1") (pinfunction "1_1") (pintype "input"))
      (node (ref "J3") (pin "1") (pinfunction "1_1") (pintype "input"))
      (node (ref "J4") (pin "1") (pinfunction "1_1") (pintype "input"))
      (node (ref "J5") (pin "1") (pinfunction "1_1") (pintype "input"))
      (node (ref "J6") (pin "1") (pinfunction "1_1") (pintype "input"))
      (node (ref "J7") (pin "1") (pinfunction "1_1") (pintype "input"))
      (node (ref "J8") (pin "1") (pinfunction "1_1") (pintype "input"))
      (node (ref "J9") (pin "1") (pinfunction "1_1") (pintype "input"))
      (node (ref "K1") (pin "2") (pinfunction "2_2") (pintype "input"))
      (node (ref "K2") (pin "2") (pinfunction "2_2") (pintype "input"))
      (node (ref "P2") (pin "1") (pinfunction "1_1") (pintype "input"))
      (node (ref "PLED1") (pin "2") (pinfunction "C_2") (pintype "input"))
      (node (ref "R6") (pin "2") (pinfunction "2_2") (pintype "input"))
      (node (ref "U1") (pin "1") (pinfunction "ADJ/GND_1") (pintype "input"))
      (node (ref "U2") (pin "4") (pinfunction "GND_4") (pintype "input"))
      (node (ref "U3") (pin "12") (pinfunction "VSSA_12") (pintype "input"))
      (node (ref "U3") (pin "18") (pinfunction "VSS_4_18") (pintype "input"))
      (node (ref "U3") (pin "28") (pinfunction "PB2_28") (pintype "input"))
      (node (ref "U3") (pin "31") (pinfunction "VSS_1_31") (pintype "input"))
      (node (ref "U3") (pin "47") (pinfunction "VSS_2_47") (pintype "input"))
      (node (ref "U3") (pin "63") (pinfunction "VSS_3_63") (pintype "input"))
      (node (ref "U7") (pin "4") (pinfunction "GND_4") (pintype "input"))
      (node (ref "U9") (pin "1") (pinfunction "1_1") (pintype "input"))
      (node (ref "USB") (pin "5") (pinfunction "GND_5") (pintype "input"))
      (node (ref "X1") (pin "2") (pinfunction "2_2") (pintype "input"))
    )
    (net (code "52") (name "Net-(CH340C-D+)") (class "Default")
      (node (ref "CH340C") (pin "5") (pinfunction "D+_5") (pintype "input"))
      (node (ref "USB") (pin "3") (pinfunction "D+_3") (pintype "input"))
    )
    (net (code "53") (name "Net-(CH340C-D-)") (class "Default")
      (node (ref "CH340C") (pin "6") (pinfunction "D-_6") (pintype "input"))
      (node (ref "USB") (pin "2") (pinfunction "D-_2") (pintype "input"))
    )
    (net (code "54") (name "Net-(D2-K)") (class "Default")
      (node (ref "D2") (pin "1") (pinfunction "K_1") (pintype "input"))
      (node (ref "L5") (pin "1") (pinfunction "1_1") (pintype "input"))
      (node (ref "U2") (pin "3") (pinfunction "SW_3") (pintype "input"))
    )
    (net (code "55") (name "Net-(J1-Pad3)") (class "Default")
      (node (ref "J1") (pin "3") (pinfunction "3_3") (pintype "input"))
      (node (ref "R20") (pin "1") (pinfunction "1_1") (pintype "input"))
    )
    (net (code "56") (name "Net-(J2-Pad3)") (class "Default")
      (node (ref "J2") (pin "3") (pinfunction "3_3") (pintype "input"))
      (node (ref "R21") (pin "1") (pinfunction "1_1") (pintype "input"))
    )
    (net (code "57") (name "Net-(J3-Pad3)") (class "Default")
      (node (ref "J3") (pin "3") (pinfunction "3_3") (pintype "input"))
      (node (ref "R22") (pin "1") (pinfunction "1_1") (pintype "input"))
    )
    (net (code "58") (name "Net-(J4-Pad3)") (class "Default")
      (node (ref "J4") (pin "3") (pinfunction "3_3") (pintype "input"))
      (node (ref "R23") (pin "1") (pinfunction "1_1") (pintype "input"))
    )
    (net (code "59") (name "Net-(J5-Pad3)") (class "Default")
      (node (ref "J5") (pin "3") (pinfunction "3_3") (pintype "input"))
      (node (ref "R24") (pin "1") (pinfunction "1_1") (pintype "input"))
    )
    (net (code "60") (name "Net-(J6-Pad3)") (class "Default")
      (node (ref "J6") (pin "3") (pinfunction "3_3") (pintype "input"))
      (node (ref "R25") (pin "1") (pinfunction "1_1") (pintype "input"))
    )
    (net (code "61") (name "Net-(J7-Pad3)") (class "Default")
      (node (ref "J7") (pin "3") (pinfunction "3_3") (pintype "input"))
      (node (ref "R26") (pin "1") (pinfunction "1_1") (pintype "input"))
    )
    (net (code "62") (name "Net-(J8-Pad3)") (class "Default")
      (node (ref "J8") (pin "3") (pinfunction "3_3") (pintype "input"))
      (node (ref "R27") (pin "1") (pinfunction "1_1") (pintype "input"))
    )
    (net (code "63") (name "Net-(J9-Pad3)") (class "Default")
      (node (ref "J9") (pin "3") (pinfunction "3_3") (pintype "input"))
      (node (ref "R28") (pin "1") (pinfunction "1_1") (pintype "input"))
    )
    (net (code "64") (name "Net-(J10-Pad3)") (class "Default")
      (node (ref "J10") (pin "3") (pinfunction "3_3") (pintype "input"))
      (node (ref "R29") (pin "1") (pinfunction "1_1") (pintype "input"))
    )
    (net (code "65") (name "Net-(J11-Pad3)") (class "Default")
      (node (ref "J11") (pin "3") (pinfunction "3_3") (pintype "input"))
      (node (ref "R30") (pin "1") (pinfunction "1_1") (pintype "input"))
    )
    (net (code "66") (name "Net-(J12-Pad3)") (class "Default")
      (node (ref "J12") (pin "3") (pinfunction "3_3") (pintype "input"))
      (node (ref "R31") (pin "1") (pinfunction "1_1") (pintype "input"))
    )
    (net (code "67") (name "Net-(J13-Pad3)") (class "Default")
      (node (ref "J13") (pin "3") (pinfunction "3_3") (pintype "input"))
      (node (ref "R32") (pin "1") (pinfunction "1_1") (pintype "input"))
    )
    (net (code "68") (name "Net-(J14-Pad3)") (class "Default")
      (node (ref "J14") (pin "3") (pinfunction "3_3") (pintype "input"))
      (node (ref "R33") (pin "1") (pinfunction "1_1") (pintype "input"))
    )
    (net (code "69") (name "Net-(J15-Pad3)") (class "Default")
      (node (ref "J15") (pin "3") (pinfunction "3_3") (pintype "input"))
      (node (ref "R34") (pin "1") (pinfunction "1_1") (pintype "input"))
    )
    (net (code "70") (name "Net-(J16-Pad3)") (class "Default")
      (node (ref "J16") (pin "3") (pinfunction "3_3") (pintype "input"))
      (node (ref "R35") (pin "1") (pinfunction "1_1") (pintype "input"))
    )
    (net (code "71") (name "Net-(J17-Pad3)") (class "Default")
      (node (ref "J17") (pin "3") (pinfunction "3_3") (pintype "input"))
      (node (ref "R36") (pin "1") (pinfunction "1_1") (pintype "input"))
    )
    (net (code "72") (name "Net-(J18-Pad3)") (class "Default")
      (node (ref "J18") (pin "3") (pinfunction "3_3") (pintype "input"))
      (node (ref "R37") (pin "1") (pinfunction "1_1") (pintype "input"))
    )
    (net (code "73") (name "Net-(J19-Pad3)") (class "Default")
      (node (ref "J19") (pin "3") (pinfunction "3_3") (pintype "input"))
      (node (ref "R38") (pin "1") (pinfunction "1_1") (pintype "input"))
    )
    (net (code "74") (name "Net-(J20-Pad3)") (class "Default")
      (node (ref "J20") (pin "3") (pinfunction "3_3") (pintype "input"))
      (node (ref "R39") (pin "1") (pinfunction "1_1") (pintype "input"))
    )
    (net (code "75") (name "Net-(J21-Pad3)") (class "Default")
      (node (ref "J21") (pin "3") (pinfunction "3_3") (pintype "input"))
      (node (ref "R40") (pin "1") (pinfunction "1_1") (pintype "input"))
    )
    (net (code "76") (name "Net-(J22-Pad3)") (class "Default")
      (node (ref "J22") (pin "3") (pinfunction "3_3") (pintype "input"))
      (node (ref "R41") (pin "1") (pinfunction "1_1") (pintype "input"))
    )
    (net (code "77") (name "Net-(J23-Pad3)") (class "Default")
      (node (ref "J23") (pin "3") (pinfunction "3_3") (pintype "input"))
      (node (ref "R42") (pin "1") (pinfunction "1_1") (pintype "input"))
    )
    (net (code "78") (name "Net-(J24-Pad3)") (class "Default")
      (node (ref "J24") (pin "3") (pinfunction "3_3") (pintype "input"))
      (node (ref "R43") (pin "1") (pinfunction "1_1") (pintype "input"))
    )
    (net (code "79") (name "Net-(P2-Pad2)") (class "Default")
      (node (ref "P2") (pin "2") (pinfunction "2_2") (pintype "input"))
      (node (ref "SW1") (pin "3") (pinfunction "3_3") (pintype "input"))
    )
    (net (code "80") (name "Net-(PLED1-A)") (class "Default")
      (node (ref "PLED1") (pin "1") (pinfunction "A_1") (pintype "input"))
      (node (ref "R1") (pin "1") (pinfunction "1_1") (pintype "input"))
    )
    (net (code "81") (name "Net-(PLED2-A)") (class "Default")
      (node (ref "PLED2") (pin "1") (pinfunction "A_1") (pintype "input"))
      (node (ref "R10") (pin "1") (pinfunction "1_1") (pintype "input"))
    )
    (net (code "82") (name "Net-(SS34-A)") (class "Default")
      (node (ref "SS34") (pin "2") (pinfunction "A_2") (pintype "input"))
      (node (ref "USB") (pin "1") (pinfunction "VBUS_1") (pintype "input"))
    )
    (net (code "83") (name "Net-(U2-FB)") (class "Default")
      (node (ref "R13") (pin "2") (pinfunction "2_2") (pintype "input"))
      (node (ref "R6") (pin "1") (pinfunction "1_1") (pintype "input"))
      (node (ref "U2") (pin "5") (pinfunction "FB_5") (pintype "input"))
    )
    (net (code "84") (name "Net-(U7-HOLD#orRESET#(IO3))") (class "Default")
      (node (ref "R11") (pin "1") (pinfunction "1_1") (pintype "input"))
      (node (ref "U7") (pin "7") (pinfunction "HOLD#orRESET#(IO3)_7") (pintype "input"))
    )
    (net (code "85") (name "Net-(U7-WP#(IO2))") (class "Default")
      (node (ref "R12") (pin "1") (pinfunction "1_1") (pintype "input"))
      (node (ref "U7") (pin "3") (pinfunction "WP#(IO2)_3") (pintype "input"))
    )
    (net (code "86") (name "unconnected-(BOOT0-Pad4)") (class "Default")
      (node (ref "BOOT0") (pin "4") (pinfunction "4_4") (pintype "input+no_connect"))
    )
    (net (code "87") (name "unconnected-(BOOT0-Pad5)") (class "Default")
      (node (ref "BOOT0") (pin "5") (pinfunction "5_5") (pintype "input+no_connect"))
    )
    (net (code "88") (name "unconnected-(CH340C-CTS#-Pad9)") (class "Default")
      (node (ref "CH340C") (pin "9") (pinfunction "CTS#_9") (pintype "input+no_connect"))
    )
    (net (code "89") (name "unconnected-(CH340C-DCD#-Pad12)") (class "Default")
      (node (ref "CH340C") (pin "12") (pinfunction "DCD#_12") (pintype "input+no_connect"))
    )
    (net (code "90") (name "unconnected-(CH340C-DSR#-Pad10)") (class "Default")
      (node (ref "CH340C") (pin "10") (pinfunction "DSR#_10") (pintype "input+no_connect"))
    )
    (net (code "91") (name "unconnected-(CH340C-DTR#-Pad13)") (class "Default")
      (node (ref "CH340C") (pin "13") (pinfunction "DTR#_13") (pintype "input+no_connect"))
    )
    (net (code "92") (name "unconnected-(CH340C-NC.-Pad7)") (class "Default")
      (node (ref "CH340C") (pin "7") (pinfunction "NC._7") (pintype "input+no_connect"))
    )
    (net (code "93") (name "unconnected-(CH340C-NC.-Pad8)") (class "Default")
      (node (ref "CH340C") (pin "8") (pinfunction "NC._8") (pintype "input+no_connect"))
    )
    (net (code "94") (name "unconnected-(CH340C-R232-Pad15)") (class "Default")
      (node (ref "CH340C") (pin "15") (pinfunction "R232_15") (pintype "input+no_connect"))
    )
    (net (code "95") (name "unconnected-(CH340C-RI#-Pad11)") (class "Default")
      (node (ref "CH340C") (pin "11") (pinfunction "RI#_11") (pintype "input+no_connect"))
    )
    (net (code "96") (name "unconnected-(CH340C-RTS#-Pad14)") (class "Default")
      (node (ref "CH340C") (pin "14") (pinfunction "RTS#_14") (pintype "input+no_connect"))
    )
    (net (code "97") (name "unconnected-(SW1-Pad1)") (class "Default")
      (node (ref "SW1") (pin "1") (pinfunction "1_1") (pintype "input+no_connect"))
    )
    (net (code "98") (name "unconnected-(U1-VOUT-Pad4)") (class "Default")
      (node (ref "U1") (pin "4") (pinfunction "VOUT_4") (pintype "input+no_connect"))
    )
    (net (code "99") (name "unconnected-(U2-NC-Pad1)") (class "Default")
      (node (ref "U2") (pin "1") (pinfunction "NC_1") (pintype "input+no_connect"))
    )
    (net (code "100") (name "unconnected-(U2-NC-Pad6)") (class "Default")
      (node (ref "U2") (pin "6") (pinfunction "NC_6") (pintype "input+no_connect"))
    )
    (net (code "101") (name "unconnected-(U2-NC-Pad8)") (class "Default")
      (node (ref "U2") (pin "8") (pinfunction "NC_8") (pintype "input+no_connect"))
    )
    (net (code "102") (name "unconnected-(U3-PA3-Pad17)") (class "Default")
      (node (ref "U3") (pin "17") (pinfunction "PA3_17") (pintype "input+no_connect"))
    )
    (net (code "103") (name "unconnected-(U3-PA4-Pad20)") (class "Default")
      (node (ref "U3") (pin "20") (pinfunction "PA4_20") (pintype "input+no_connect"))
    )
    (net (code "104") (name "unconnected-(U3-PA13-Pad46)") (class "Default")
      (node (ref "U3") (pin "46") (pinfunction "PA13_46") (pintype "input+no_connect"))
    )
    (net (code "105") (name "unconnected-(U3-PB13-Pad34)") (class "Default")
      (node (ref "U3") (pin "34") (pinfunction "PB13_34") (pintype "input+no_connect"))
    )
    (net (code "106") (name "unconnected-(U3-PC14-OSC32_IN-Pad3)") (class "Default")
      (node (ref "U3") (pin "3") (pinfunction "PC14-OSC32_IN_3") (pintype "input+no_connect"))
    )
    (net (code "107") (name "unconnected-(U3-PC15-OSC32_OUT-Pad4)") (class "Default")
      (node (ref "U3") (pin "4") (pinfunction "PC15-OSC32_OUT_4") (pintype "input+no_connect"))
    )
    (net (code "108") (name "unconnected-(USB-ID-Pad4)") (class "Default")
      (node (ref "USB") (pin "4") (pinfunction "ID_4") (pintype "input+no_connect"))
    )
    (net (code "109") (name "unconnected-(USB-SH1-Pad6)") (class "Default")
      (node (ref "USB") (pin "6") (pinfunction "SH1_6") (pintype "input+no_connect"))
    )
    (net (code "110") (name "unconnected-(USB-SH2-Pad7)") (class "Default")
      (node (ref "USB") (pin "7") (pinfunction "SH2_7") (pintype "input+no_connect"))
    )
    (net (code "111") (name "unconnected-(USB-SH3-Pad8)") (class "Default")
      (node (ref "USB") (pin "8") (pinfunction "SH3_8") (pintype "input+no_connect"))
    )
    (net (code "112") (name "unconnected-(USB-SH4-Pad9)") (class "Default")
      (node (ref "USB") (pin "9") (pinfunction "SH4_9") (pintype "input+no_connect"))
    )
  )
)
